# v1_3.net
KiCad netlist of a schematic drawn in Altium Designer
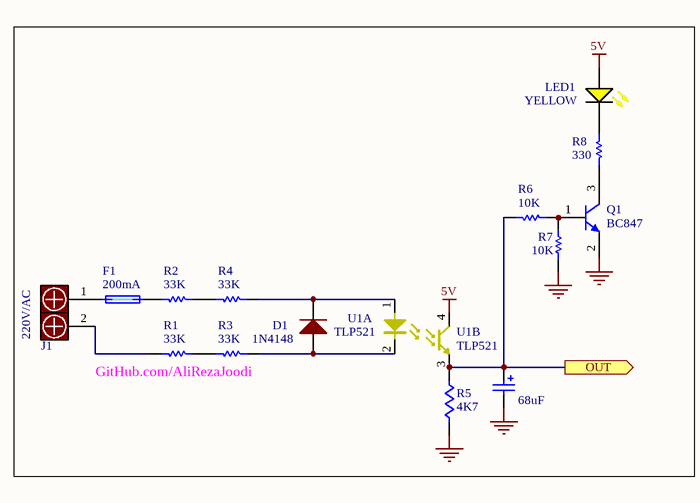
[diagram p0: v1.3.SchDoc]

(export (version "E")
  (design (tool "Eeschema 10.0.6"))
  (components
    (comp (ref "C1")
      (value "68uF")
      (footprint "Cap_D")
      (description "Polarized Capacitor (Radial)")
      (fields
        (field (name "MANUFACTURER") "Generic Components")
        (field (name "Comment") "CAP")
        (field (name "PUBLISHER") "Altium Limited")
      )
      (libsource (lib "Miscellaneous Devices") (part "Cap Pol1"))
    )
    (comp (ref "D1")
      (value "1N4148")
      (footprint "SMD_DO-213AA")
      (description "Diode")
      (fields (field (name "1_PART NUMBER") "1N4148UR-1"))
      (libsource (lib "General") (part "Diode_2Form"))
    )
    (comp (ref "F1")
      (value "200mA")
      (footprint "SMD_1206")
      (description "Fuse")
      (fields (field (name "1_PART NUMBER") "0437.250WRA"))
      (libsource (lib "General") (part "Fuse"))
    )
    (comp (ref "J1")
      (value "Connector1x2_Power_4Form")
      (footprint "1x2_P8.26")
      (description "Connector, Barrier Terminal Blocks, 2Pin")
      (fields (field (name "1_PART NUMBER") "1977477-2"))
      (libsource (lib "Connector") (part "Connector1x2_Power_4Form"))
    )
    (comp (ref "LED1")
      (value "YELLOW")
      (footprint "SMD_0805_YELLOW")
      (description "LED")
      (libsource (lib "Display") (part "LED_YELLOW"))
    )
    (comp (ref "Q1")
      (value "BC847")
      (footprint "SOT23-3N")
      (description "Silicon Bipolar Transistor")
      (libsource (lib "my Libraries") (part "BC847"))
    )
    (comp (ref "R1")
      (value "33K")
      (description "Resistor, 1/4W, 5%")
      (libsource (lib "") (part "Resistor_1"))
    )
    (comp (ref "R2")
      (value "33K")
      (description "Resistor, 1/4W, 5%")
      (libsource (lib "") (part "Resistor_1"))
    )
    (comp (ref "R3")
      (value "33K")
      (description "Resistor, 1/4W, 5%")
      (libsource (lib "") (part "Resistor_1"))
    )
    (comp (ref "R4")
      (value "33K")
      (description "Resistor, 1/4W, 5%")
      (libsource (lib "") (part "Resistor_1"))
    )
    (comp (ref "R5")
      (value "4K7")
      (footprint "0805")
      (description "Resistor")
      (fields (field (name "MANUFACTURER") "Generic Components") (field (name "PUBLISHER") "Altium Limited"))
      (libsource (lib "Miscellaneous Devices") (part "Res1"))
    )
    (comp (ref "R6")
      (value "10K")
      (description "Resistor, 1/4W, 5%")
      (libsource (lib "General") (part "Resistor"))
    )
    (comp (ref "R7")
      (value "10K")
      (description "Resistor, 1/4W, 5%")
      (libsource (lib "General") (part "Resistor"))
    )
    (comp (ref "R8")
      (value "330")
      (description "Resistor, 1/4W, 5%")
      (libsource (lib "General") (part "Resistor"))
    )
    (comp (ref "U1")
      (value "TLP521")
      (footprint "DIP_4")
      (description "Phototransistor")
      (fields (field (name "PUBLISHER") "Altium Limited"))
      (libsource (lib "IC") (part "Optoisolator_Transistor"))
    )
  )
  (nets
    (net (code "1") (name "/OUT") (class "Default")
      (node (ref "C1") (pin "1") (pinfunction "1_1") (pintype "passive"))
      (node (ref "R5") (pin "1") (pinfunction "1_1") (pintype "passive"))
      (node (ref "R6") (pin "1") (pinfunction "1_1") (pintype "passive"))
      (node (ref "U1") (pin "3") (pinfunction "E_3") (pintype "passive"))
    )
    (net (code "2") (name "5V") (class "Default")
      (node (ref "LED1") (pin "1") (pinfunction "A_1") (pintype "passive"))
      (node (ref "U1") (pin "4") (pinfunction "C_4") (pintype "passive"))
    )
    (net (code "3") (name "GND") (class "Default")
      (node (ref "C1") (pin "2") (pinfunction "2_2") (pintype "passive"))
      (node (ref "Q1") (pin "2") (pinfunction "E_2") (pintype "passive"))
      (node (ref "R5") (pin "2") (pinfunction "2_2") (pintype "passive"))
      (node (ref "R7") (pin "1") (pinfunction "1_1") (pintype "passive"))
    )
    (net (code "4") (name "Net-(D1-A)") (class "Default")
      (node (ref "D1") (pin "1") (pinfunction "A_1") (pintype "passive"))
      (node (ref "R3") (pin "1") (pinfunction "1_1") (pintype "passive"))
      (node (ref "U1") (pin "2") (pinfunction "K_2") (pintype "power_in"))
    )
    (net (code "5") (name "Net-(D1-K)") (class "Default")
      (node (ref "D1") (pin "2") (pinfunction "K_2") (pintype "passive"))
      (node (ref "R4") (pin "1") (pinfunction "1_1") (pintype "passive"))
      (node (ref "U1") (pin "1") (pinfunction "A_1") (pintype "power_in"))
    )
    (net (code "6") (name "Net-(F1-Pad1)") (class "Default")
      (node (ref "F1") (pin "1") (pinfunction "1_1") (pintype "passive"))
      (node (ref "J1") (pin "1") (pinfunction "1_1") (pintype "passive"))
    )
    (net (code "7") (name "Net-(F1-Pad2)") (class "Default")
      (node (ref "F1") (pin "2") (pinfunction "2_2") (pintype "passive"))
      (node (ref "R2") (pin "2") (pinfunction "2_2") (pintype "passive"))
    )
    (net (code "8") (name "Net-(J1-Pad2)") (class "Default")
      (node (ref "J1") (pin "2") (pinfunction "2_2") (pintype "passive"))
      (node (ref "R1") (pin "2") (pinfunction "2_2") (pintype "passive"))
    )
    (net (code "9") (name "Net-(LED1-K)") (class "Default")
      (node (ref "LED1") (pin "2") (pinfunction "K_2") (pintype "passive"))
      (node (ref "R8") (pin "2") (pinfunction "2_2") (pintype "passive"))
    )
    (net (code "10") (name "Net-(Q1-B)") (class "Default")
      (node (ref "Q1") (pin "1") (pinfunction "B_1") (pintype "passive"))
      (node (ref "R6") (pin "2") (pinfunction "2_2") (pintype "passive"))
      (node (ref "R7") (pin "2") (pinfunction "2_2") (pintype "passive"))
    )
    (net (code "11") (name "Net-(Q1-C)") (class "Default")
      (node (ref "Q1") (pin "3") (pinfunction "C_3") (pintype "passive"))
      (node (ref "R8") (pin "1") (pinfunction "1_1") (pintype "passive"))
    )
    (net (code "12") (name "Net-(R1-Pad1)") (class "Default")
      (node (ref "R1") (pin "1") (pinfunction "1_1") (pintype "passive"))
      (node (ref "R3") (pin "2") (pinfunction "2_2") (pintype "passive"))
    )
    (net (code "13") (name "Net-(R2-Pad1)") (class "Default")
      (node (ref "R2") (pin "1") (pinfunction "1_1") (pintype "passive"))
      (node (ref "R4") (pin "2") (pinfunction "2_2") (pintype "passive"))
    )
  )
)
